# PET_Joystick_Adapter.net
KiCad netlist of a schematic drawn in EAGLE
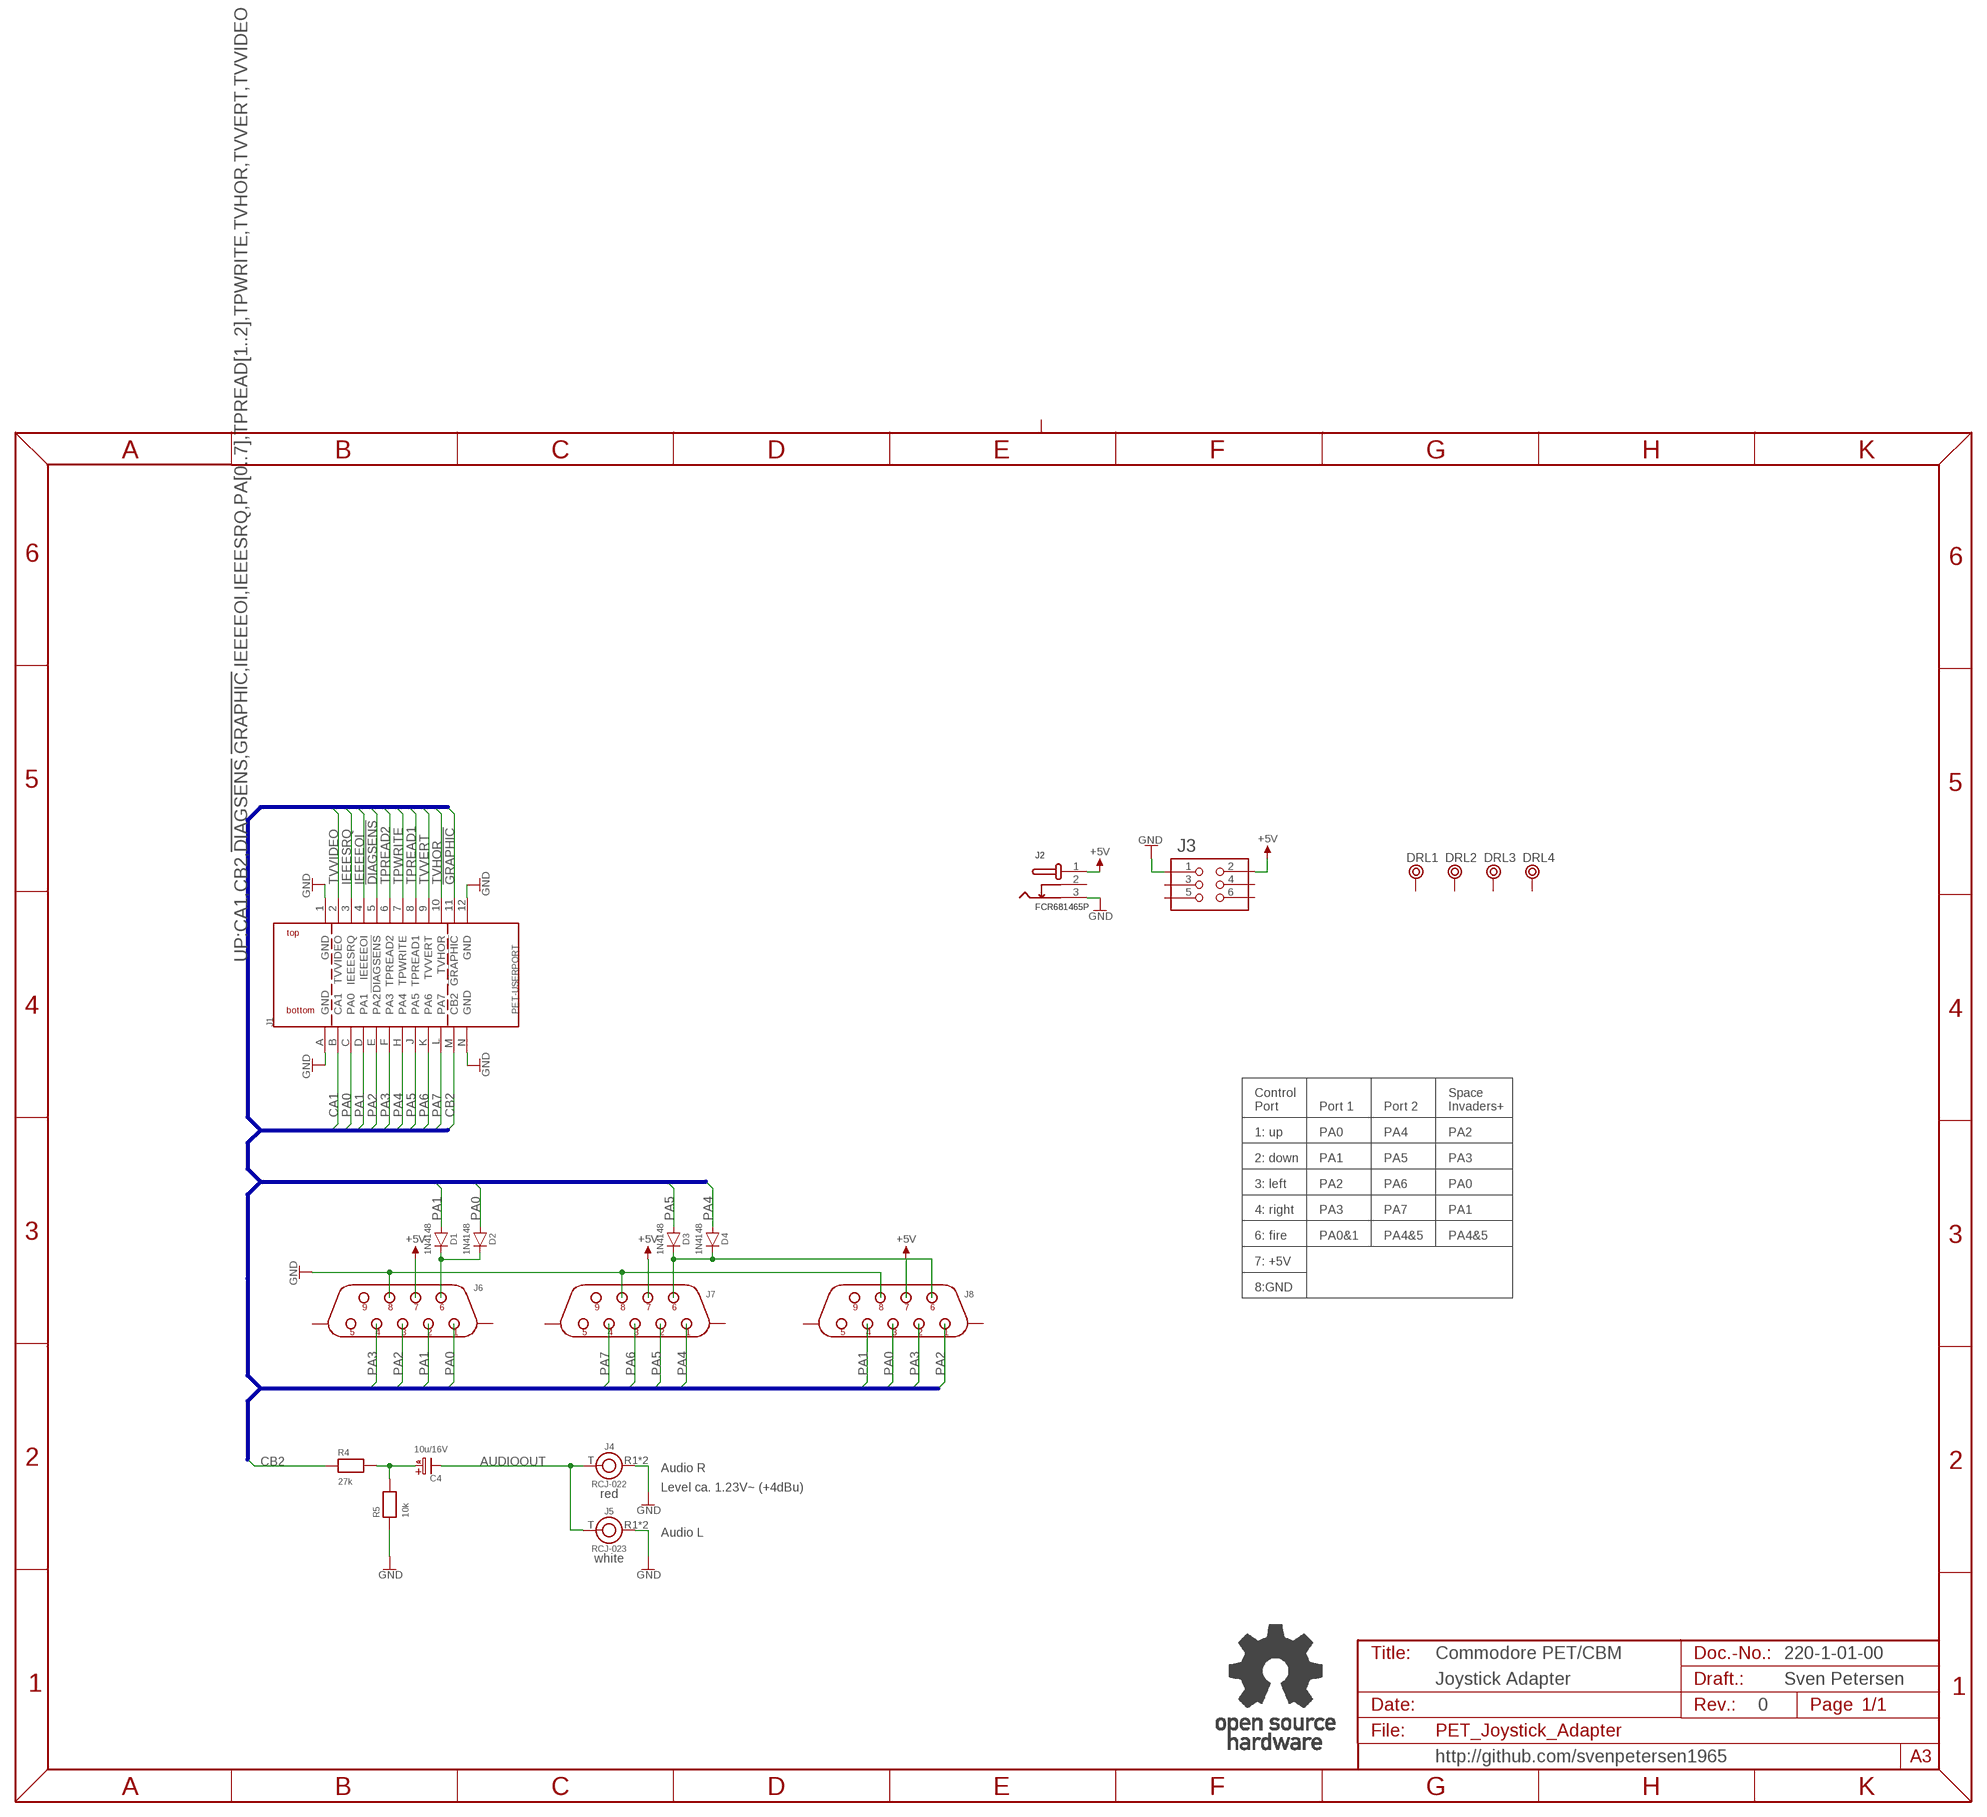
[diagram p0: schematic, sheet 1]

(export (version "E")
  (design (tool "Eeschema 10.0.6"))
  (components
    (comp (ref "C4")
      (value "10u/16V")
      (footprint "eagle-import:C5,0_2,0")
      (libsource (lib "eagle-import") (part "C05,0/2,0"))
    )
    (comp (ref "D1")
      (value "1N4148")
      (footprint "eagle-import:DO-35_3")
      (libsource (lib "eagle-import") (part "1N41480.3{dblquote}"))
    )
    (comp (ref "D2")
      (value "1N4148")
      (footprint "eagle-import:DO-35_3")
      (libsource (lib "eagle-import") (part "1N41480.3{dblquote}"))
    )
    (comp (ref "D3")
      (value "1N4148")
      (footprint "eagle-import:DO-35_3")
      (libsource (lib "eagle-import") (part "1N41480.3{dblquote}"))
    )
    (comp (ref "D4")
      (value "1N4148")
      (footprint "eagle-import:DO-35_3")
      (libsource (lib "eagle-import") (part "1N41480.3{dblquote}"))
    )
    (comp (ref "DRL1")
      (value "BOHR3,5")
      (footprint "eagle-import:BOHR3,5")
      (libsource (lib "eagle-import") (part "BOHR3,5"))
    )
    (comp (ref "DRL2")
      (value "BOHR3,5")
      (footprint "eagle-import:BOHR3,5")
      (libsource (lib "eagle-import") (part "BOHR3,5"))
    )
    (comp (ref "DRL3")
      (value "BOHR3,5")
      (footprint "eagle-import:BOHR3,5")
      (libsource (lib "eagle-import") (part "BOHR3,5"))
    )
    (comp (ref "DRL4")
      (value "BOHR3,5")
      (footprint "eagle-import:BOHR3,5")
      (libsource (lib "eagle-import") (part "BOHR3,5"))
    )
    (comp (ref "J1")
      (value "PET-USERPORT")
      (footprint "eagle-import:USERPORT")
      (libsource (lib "eagle-import") (part "PET-USERPORT"))
    )
    (comp (ref "J2")
      (value "FCR681465P")
      (footprint "eagle-import:FCR681465P")
      (libsource (lib "eagle-import") (part "FCR681465P"))
    )
    (comp (ref "J3")
      (value "2X03WV")
      (footprint "eagle-import:2X03WV")
      (libsource (lib "eagle-import") (part "2X03WV"))
    )
    (comp (ref "J4")
      (value "RCJ-022")
      (footprint "eagle-import:RCJ-02X")
      (libsource (lib "eagle-import") (part "RCJ-02X"))
    )
    (comp (ref "J5")
      (value "RCJ-023")
      (footprint "eagle-import:RCJ-02X")
      (libsource (lib "eagle-import") (part "RCJ-02X"))
    )
    (comp (ref "J6")
      (value "DS09M-H-CL")
      (footprint "eagle-import:DS9M-H")
      (libsource (lib "eagle-import") (part "DS09M-H-CL"))
    )
    (comp (ref "J7")
      (value "DS09M-H-CL")
      (footprint "eagle-import:DS9M-H")
      (libsource (lib "eagle-import") (part "DS09M-H-CL"))
    )
    (comp (ref "J8")
      (value "DS09M-V-CL")
      (footprint "eagle-import:DS09M-V")
      (libsource (lib "eagle-import") (part "DS09M-V-CL"))
    )
    (comp (ref "R4")
      (value "27k")
      (footprint "eagle-import:R-10")
      (libsource (lib "eagle-import") (part "RES04"))
    )
    (comp (ref "R5")
      (value "10k")
      (footprint "eagle-import:R-10")
      (libsource (lib "eagle-import") (part "RES04"))
    )
    (comp (ref "U$2")
      (value "OPEN_SOURCE_HW")
      (footprint "eagle-import:OPENHW")
      (libsource (lib "eagle-import") (part "OPEN_SOURCE_HW"))
    )
  )
  (nets
    (net (code "2") (name "+5V") (class "Default")
      (node (ref "J2") (pin "1") (pinfunction "1_1") (pintype "bidirectional"))
      (node (ref "J3") (pin "2") (pinfunction "2_2") (pintype "passive"))
      (node (ref "J6") (pin "7") (pinfunction "7_7") (pintype "passive"))
      (node (ref "J7") (pin "7") (pinfunction "7_7") (pintype "passive"))
      (node (ref "J8") (pin "7") (pinfunction "7_7") (pintype "passive"))
    )
    (net (code "3") (name "/AUDIOOUT") (class "Default")
      (node (ref "C4") (pin "K") (pinfunction "-_K") (pintype "passive"))
      (node (ref "J4") (pin "T") (pinfunction "T_T") (pintype "bidirectional"))
      (node (ref "J5") (pin "T") (pinfunction "T_T") (pintype "bidirectional"))
    )
    (net (code "4") (name "/CA1") (class "Default")
      (node (ref "J1") (pin "B") (pinfunction "CA1_B") (pintype "input"))
    )
    (net (code "5") (name "/CB2") (class "Default")
      (node (ref "J1") (pin "M") (pinfunction "CB2_M") (pintype "bidirectional"))
      (node (ref "R4") (pin "1") (pinfunction "1_1") (pintype "passive"))
    )
    (net (code "6") (name "/IEEEEOI") (class "Default")
      (node (ref "J1") (pin "4") (pinfunction "IEEEEOI_4") (pintype "output"))
    )
    (net (code "7") (name "/IEEESRQ") (class "Default")
      (node (ref "J1") (pin "3") (pinfunction "IEEESRQ_3") (pintype "output"))
    )
    (net (code "8") (name "/PA0") (class "Default")
      (node (ref "D2") (pin "A") (pinfunction "A_A") (pintype "passive"))
      (node (ref "J1") (pin "C") (pinfunction "PA0_C") (pintype "bidirectional"))
      (node (ref "J6") (pin "1") (pinfunction "1_1") (pintype "passive"))
      (node (ref "J8") (pin "3") (pinfunction "3_3") (pintype "passive"))
    )
    (net (code "9") (name "/PA1") (class "Default")
      (node (ref "D1") (pin "A") (pinfunction "A_A") (pintype "passive"))
      (node (ref "J1") (pin "D") (pinfunction "PA1_D") (pintype "bidirectional"))
      (node (ref "J6") (pin "2") (pinfunction "2_2") (pintype "passive"))
      (node (ref "J8") (pin "4") (pinfunction "4_4") (pintype "passive"))
    )
    (net (code "10") (name "/PA2") (class "Default")
      (node (ref "J1") (pin "E") (pinfunction "PA2_E") (pintype "bidirectional"))
      (node (ref "J6") (pin "3") (pinfunction "3_3") (pintype "passive"))
      (node (ref "J8") (pin "1") (pinfunction "1_1") (pintype "passive"))
    )
    (net (code "11") (name "/PA3") (class "Default")
      (node (ref "J1") (pin "F") (pinfunction "PA3_F") (pintype "bidirectional"))
      (node (ref "J6") (pin "4") (pinfunction "4_4") (pintype "passive"))
      (node (ref "J8") (pin "2") (pinfunction "2_2") (pintype "passive"))
    )
    (net (code "12") (name "/PA4") (class "Default")
      (node (ref "D4") (pin "A") (pinfunction "A_A") (pintype "passive"))
      (node (ref "J1") (pin "H") (pinfunction "PA4_H") (pintype "bidirectional"))
      (node (ref "J7") (pin "1") (pinfunction "1_1") (pintype "passive"))
    )
    (net (code "13") (name "/PA5") (class "Default")
      (node (ref "D3") (pin "A") (pinfunction "A_A") (pintype "passive"))
      (node (ref "J1") (pin "J") (pinfunction "PA5_J") (pintype "bidirectional"))
      (node (ref "J7") (pin "2") (pinfunction "2_2") (pintype "passive"))
    )
    (net (code "14") (name "/PA6") (class "Default")
      (node (ref "J1") (pin "K") (pinfunction "PA6_K") (pintype "bidirectional"))
      (node (ref "J7") (pin "3") (pinfunction "3_3") (pintype "passive"))
    )
    (net (code "15") (name "/PA7") (class "Default")
      (node (ref "J1") (pin "L") (pinfunction "PA7_L") (pintype "bidirectional"))
      (node (ref "J7") (pin "4") (pinfunction "4_4") (pintype "passive"))
    )
    (net (code "16") (name "/TPREAD1") (class "Default")
      (node (ref "J1") (pin "8") (pinfunction "TPREAD1_8") (pintype "output"))
    )
    (net (code "17") (name "/TPREAD2") (class "Default")
      (node (ref "J1") (pin "6") (pinfunction "TPREAD2_6") (pintype "output"))
    )
    (net (code "18") (name "/TPWRITE") (class "Default")
      (node (ref "J1") (pin "7") (pinfunction "TPWRITE_7") (pintype "output"))
    )
    (net (code "19") (name "/TVHOR") (class "Default")
      (node (ref "J1") (pin "10") (pinfunction "TVHOR_10") (pintype "output"))
    )
    (net (code "20") (name "/TVVERT") (class "Default")
      (node (ref "J1") (pin "9") (pinfunction "TVVERT_9") (pintype "output"))
    )
    (net (code "21") (name "/TVVIDEO") (class "Default")
      (node (ref "J1") (pin "2") (pinfunction "TVVIDEO_2") (pintype "output"))
    )
    (net (code "23") (name "/~{DIAGSENS}") (class "Default")
      (node (ref "J1") (pin "5") (pinfunction "~{DIAGSENS}_5") (pintype "output"))
    )
    (net (code "24") (name "/~{GRAPHIC}") (class "Default")
      (node (ref "J1") (pin "11") (pinfunction "~{GRAPHIC}_11") (pintype "output"))
    )
    (net (code "25") (name "GND") (class "Default")
      (node (ref "J1") (pin "1") (pinfunction "GND_1") (pintype "power_in"))
      (node (ref "J1") (pin "12") (pinfunction "GND_12") (pintype "power_in"))
      (node (ref "J1") (pin "A") (pinfunction "GND_A") (pintype "power_in"))
      (node (ref "J1") (pin "N") (pinfunction "GND_N") (pintype "power_in"))
      (node (ref "J2") (pin "3") (pinfunction "3_3") (pintype "bidirectional"))
      (node (ref "J3") (pin "1") (pinfunction "1_1") (pintype "passive"))
      (node (ref "J4") (pin "R1") (pinfunction "R_R1") (pintype "bidirectional"))
      (node (ref "J4") (pin "R2") (pinfunction "R_R2") (pintype "bidirectional"))
      (node (ref "J5") (pin "R1") (pinfunction "R_R1") (pintype "bidirectional"))
      (node (ref "J5") (pin "R2") (pinfunction "R_R2") (pintype "bidirectional"))
      (node (ref "J6") (pin "8") (pinfunction "8_8") (pintype "passive"))
      (node (ref "J7") (pin "8") (pinfunction "8_8") (pintype "passive"))
      (node (ref "J8") (pin "8") (pinfunction "8_8") (pintype "passive"))
      (node (ref "R5") (pin "1") (pinfunction "1_1") (pintype "passive"))
    )
    (net (code "26") (name "Net-(C4-+)") (class "Default")
      (node (ref "C4") (pin "A") (pinfunction "+_A") (pintype "passive"))
      (node (ref "R4") (pin "2") (pinfunction "2_2") (pintype "passive"))
      (node (ref "R5") (pin "2") (pinfunction "2_2") (pintype "passive"))
    )
    (net (code "27") (name "Net-(D1-PadK)") (class "Default")
      (node (ref "D1") (pin "K") (pinfunction "K_K") (pintype "passive"))
      (node (ref "D2") (pin "K") (pinfunction "K_K") (pintype "passive"))
      (node (ref "J6") (pin "6") (pinfunction "6_6") (pintype "passive"))
    )
    (net (code "28") (name "Net-(D3-PadK)") (class "Default")
      (node (ref "D3") (pin "K") (pinfunction "K_K") (pintype "passive"))
      (node (ref "D4") (pin "K") (pinfunction "K_K") (pintype "passive"))
      (node (ref "J7") (pin "6") (pinfunction "6_6") (pintype "passive"))
      (node (ref "J8") (pin "6") (pinfunction "6_6") (pintype "passive"))
    )
    (net (code "29") (name "unconnected-(DRL1-PadP$1)") (class "Default")
      (node (ref "DRL1") (pin "P$1") (pinfunction "P$1_P$1") (pintype "passive"))
    )
    (net (code "30") (name "unconnected-(DRL2-PadP$1)") (class "Default")
      (node (ref "DRL2") (pin "P$1") (pinfunction "P$1_P$1") (pintype "passive"))
    )
    (net (code "31") (name "unconnected-(DRL3-PadP$1)") (class "Default")
      (node (ref "DRL3") (pin "P$1") (pinfunction "P$1_P$1") (pintype "passive"))
    )
    (net (code "32") (name "unconnected-(DRL4-PadP$1)") (class "Default")
      (node (ref "DRL4") (pin "P$1") (pinfunction "P$1_P$1") (pintype "passive"))
    )
    (net (code "33") (name "unconnected-(J2-Pad2)") (class "Default")
      (node (ref "J2") (pin "2") (pinfunction "2_2") (pintype "bidirectional"))
    )
    (net (code "34") (name "unconnected-(J3-Pad3)") (class "Default")
      (node (ref "J3") (pin "3") (pinfunction "3_3") (pintype "passive"))
    )
    (net (code "35") (name "unconnected-(J3-Pad4)") (class "Default")
      (node (ref "J3") (pin "4") (pinfunction "4_4") (pintype "passive"))
    )
    (net (code "36") (name "unconnected-(J3-Pad5)") (class "Default")
      (node (ref "J3") (pin "5") (pinfunction "5_5") (pintype "passive"))
    )
    (net (code "37") (name "unconnected-(J3-Pad6)") (class "Default")
      (node (ref "J3") (pin "6") (pinfunction "6_6") (pintype "passive"))
    )
    (net (code "38") (name "unconnected-(J6-P$1-PadPE1)") (class "Default")
      (node (ref "J6") (pin "PE1") (pinfunction "P$1_PE1") (pintype "passive"))
    )
    (net (code "39") (name "unconnected-(J6-P$2-PadPE2)") (class "Default")
      (node (ref "J6") (pin "PE2") (pinfunction "P$2_PE2") (pintype "passive"))
    )
    (net (code "40") (name "unconnected-(J6-Pad5)") (class "Default")
      (node (ref "J6") (pin "5") (pinfunction "5_5") (pintype "passive"))
    )
    (net (code "41") (name "unconnected-(J6-Pad9)") (class "Default")
      (node (ref "J6") (pin "9") (pinfunction "9_9") (pintype "passive"))
    )
    (net (code "42") (name "unconnected-(J7-P$1-PadPE1)") (class "Default")
      (node (ref "J7") (pin "PE1") (pinfunction "P$1_PE1") (pintype "passive"))
    )
    (net (code "43") (name "unconnected-(J7-P$2-PadPE2)") (class "Default")
      (node (ref "J7") (pin "PE2") (pinfunction "P$2_PE2") (pintype "passive"))
    )
    (net (code "44") (name "unconnected-(J7-Pad5)") (class "Default")
      (node (ref "J7") (pin "5") (pinfunction "5_5") (pintype "passive"))
    )
    (net (code "45") (name "unconnected-(J7-Pad9)") (class "Default")
      (node (ref "J7") (pin "9") (pinfunction "9_9") (pintype "passive"))
    )
    (net (code "46") (name "unconnected-(J8-P$1-PadPE1)") (class "Default")
      (node (ref "J8") (pin "PE1") (pinfunction "P$1_PE1") (pintype "passive"))
    )
    (net (code "47") (name "unconnected-(J8-P$2-PadPE2)") (class "Default")
      (node (ref "J8") (pin "PE2") (pinfunction "P$2_PE2") (pintype "passive"))
    )
    (net (code "48") (name "unconnected-(J8-Pad5)") (class "Default")
      (node (ref "J8") (pin "5") (pinfunction "5_5") (pintype "passive"))
    )
    (net (code "49") (name "unconnected-(J8-Pad9)") (class "Default")
      (node (ref "J8") (pin "9") (pinfunction "9_9") (pintype "passive"))
    )
  )
)
